# BlinkenPanel.net
KiCad netlist of a schematic drawn in EAGLE
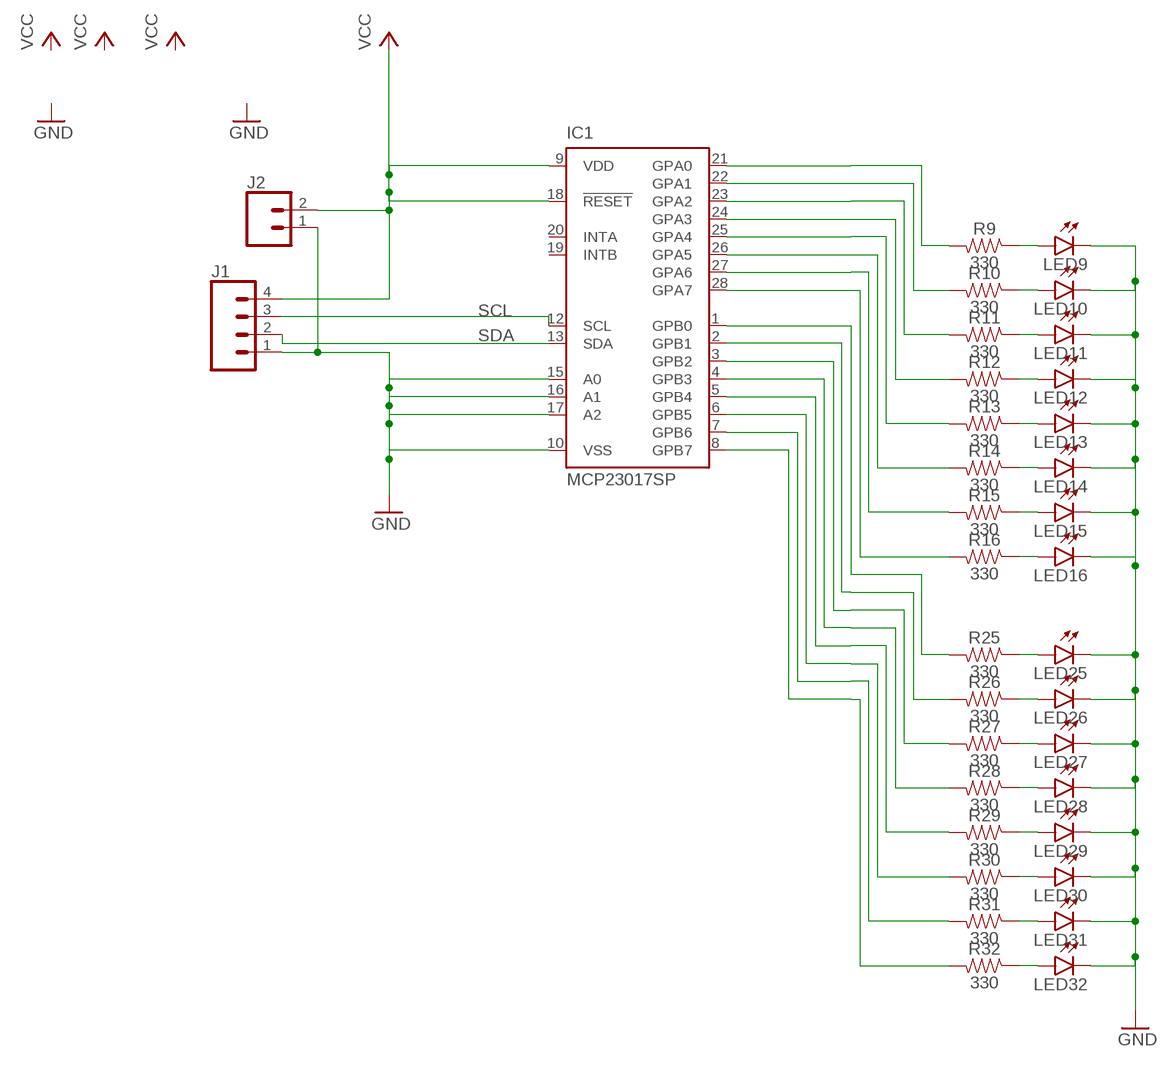
[diagram p0: schematic, sheet 1]

(export (version "E")
  (design (tool "Eeschema 10.0.6"))
  (components
    (comp (ref "IC1")
      (value "MCP23017SP")
      (footprint "eagle-import:DIL28-3")
      (fields (field (name "MF") "MICROCHIP") (field (name "MPN") "MCP23017-E/SP"))
      (libsource (lib "eagle-import") (part "MCP23017SP"))
    )
    (comp (ref "J1")
      (value "CONN_04LOCK")
      (footprint "eagle-import:1X04_LOCK")
      (libsource (lib "eagle-import") (part "CONN_04LOCK"))
    )
    (comp (ref "J2")
      (value "CONN_02")
      (footprint "eagle-import:1X02")
      (libsource (lib "eagle-import") (part "CONN_02"))
    )
    (comp (ref "LED9")
      (value "LED3MM")
      (footprint "eagle-import:LED3MM")
      (libsource (lib "eagle-import") (part "LED3MM"))
    )
    (comp (ref "LED10")
      (value "LED3MM")
      (footprint "eagle-import:LED3MM")
      (libsource (lib "eagle-import") (part "LED3MM"))
    )
    (comp (ref "LED11")
      (value "LED3MM")
      (footprint "eagle-import:LED3MM")
      (libsource (lib "eagle-import") (part "LED3MM"))
    )
    (comp (ref "LED12")
      (value "LED3MM")
      (footprint "eagle-import:LED3MM")
      (libsource (lib "eagle-import") (part "LED3MM"))
    )
    (comp (ref "LED13")
      (value "LED3MM")
      (footprint "eagle-import:LED3MM")
      (libsource (lib "eagle-import") (part "LED3MM"))
    )
    (comp (ref "LED14")
      (value "LED3MM")
      (footprint "eagle-import:LED3MM")
      (libsource (lib "eagle-import") (part "LED3MM"))
    )
    (comp (ref "LED15")
      (value "LED3MM")
      (footprint "eagle-import:LED3MM")
      (libsource (lib "eagle-import") (part "LED3MM"))
    )
    (comp (ref "LED16")
      (value "LED3MM")
      (footprint "eagle-import:LED3MM")
      (libsource (lib "eagle-import") (part "LED3MM"))
    )
    (comp (ref "LED25")
      (value "LED3MM")
      (footprint "eagle-import:LED3MM")
      (libsource (lib "eagle-import") (part "LED3MM"))
    )
    (comp (ref "LED26")
      (value "LED3MM")
      (footprint "eagle-import:LED3MM")
      (libsource (lib "eagle-import") (part "LED3MM"))
    )
    (comp (ref "LED27")
      (value "LED3MM")
      (footprint "eagle-import:LED3MM")
      (libsource (lib "eagle-import") (part "LED3MM"))
    )
    (comp (ref "LED28")
      (value "LED3MM")
      (footprint "eagle-import:LED3MM")
      (libsource (lib "eagle-import") (part "LED3MM"))
    )
    (comp (ref "LED29")
      (value "LED3MM")
      (footprint "eagle-import:LED3MM")
      (libsource (lib "eagle-import") (part "LED3MM"))
    )
    (comp (ref "LED30")
      (value "LED3MM")
      (footprint "eagle-import:LED3MM")
      (libsource (lib "eagle-import") (part "LED3MM"))
    )
    (comp (ref "LED31")
      (value "LED3MM")
      (footprint "eagle-import:LED3MM")
      (libsource (lib "eagle-import") (part "LED3MM"))
    )
    (comp (ref "LED32")
      (value "LED3MM")
      (footprint "eagle-import:LED3MM")
      (libsource (lib "eagle-import") (part "LED3MM"))
    )
    (comp (ref "R9")
      (value "330")
      (footprint "eagle-import:0603")
      (libsource (lib "eagle-import") (part "330OHM-0603-1/10W-1%"))
    )
    (comp (ref "R10")
      (value "330")
      (footprint "eagle-import:0603")
      (libsource (lib "eagle-import") (part "330OHM-0603-1/10W-1%"))
    )
    (comp (ref "R11")
      (value "330")
      (footprint "eagle-import:0603")
      (libsource (lib "eagle-import") (part "330OHM-0603-1/10W-1%"))
    )
    (comp (ref "R12")
      (value "330")
      (footprint "eagle-import:0603")
      (libsource (lib "eagle-import") (part "330OHM-0603-1/10W-1%"))
    )
    (comp (ref "R13")
      (value "330")
      (footprint "eagle-import:0603")
      (libsource (lib "eagle-import") (part "330OHM-0603-1/10W-1%"))
    )
    (comp (ref "R14")
      (value "330")
      (footprint "eagle-import:0603")
      (libsource (lib "eagle-import") (part "330OHM-0603-1/10W-1%"))
    )
    (comp (ref "R15")
      (value "330")
      (footprint "eagle-import:0603")
      (libsource (lib "eagle-import") (part "330OHM-0603-1/10W-1%"))
    )
    (comp (ref "R16")
      (value "330")
      (footprint "eagle-import:0603")
      (libsource (lib "eagle-import") (part "330OHM-0603-1/10W-1%"))
    )
    (comp (ref "R25")
      (value "330")
      (footprint "eagle-import:0603")
      (libsource (lib "eagle-import") (part "330OHM-0603-1/10W-1%"))
    )
    (comp (ref "R26")
      (value "330")
      (footprint "eagle-import:0603")
      (libsource (lib "eagle-import") (part "330OHM-0603-1/10W-1%"))
    )
    (comp (ref "R27")
      (value "330")
      (footprint "eagle-import:0603")
      (libsource (lib "eagle-import") (part "330OHM-0603-1/10W-1%"))
    )
    (comp (ref "R28")
      (value "330")
      (footprint "eagle-import:0603")
      (libsource (lib "eagle-import") (part "330OHM-0603-1/10W-1%"))
    )
    (comp (ref "R29")
      (value "330")
      (footprint "eagle-import:0603")
      (libsource (lib "eagle-import") (part "330OHM-0603-1/10W-1%"))
    )
    (comp (ref "R30")
      (value "330")
      (footprint "eagle-import:0603")
      (libsource (lib "eagle-import") (part "330OHM-0603-1/10W-1%"))
    )
    (comp (ref "R31")
      (value "330")
      (footprint "eagle-import:0603")
      (libsource (lib "eagle-import") (part "330OHM-0603-1/10W-1%"))
    )
    (comp (ref "R32")
      (value "330")
      (footprint "eagle-import:0603")
      (libsource (lib "eagle-import") (part "330OHM-0603-1/10W-1%"))
    )
  )
  (nets
    (net (code "1") (name "/SCL") (class "Default")
      (node (ref "IC1") (pin "12") (pinfunction "SCL_12") (pintype "input"))
      (node (ref "J1") (pin "3") (pinfunction "3_3") (pintype "passive"))
    )
    (net (code "2") (name "/SDA") (class "Default")
      (node (ref "IC1") (pin "13") (pinfunction "SDA_13") (pintype "bidirectional"))
      (node (ref "J1") (pin "2") (pinfunction "2_2") (pintype "passive"))
    )
    (net (code "3") (name "GND") (class "Default")
      (node (ref "IC1") (pin "10") (pinfunction "VSS_10") (pintype "power_in"))
      (node (ref "IC1") (pin "15") (pinfunction "A0_15") (pintype "input"))
      (node (ref "IC1") (pin "16") (pinfunction "A1_16") (pintype "input"))
      (node (ref "IC1") (pin "17") (pinfunction "A2_17") (pintype "input"))
      (node (ref "J1") (pin "1") (pinfunction "1_1") (pintype "passive"))
      (node (ref "J2") (pin "1") (pinfunction "1_1") (pintype "passive"))
      (node (ref "LED10") (pin "K") (pinfunction "C_K") (pintype "passive"))
      (node (ref "LED11") (pin "K") (pinfunction "C_K") (pintype "passive"))
      (node (ref "LED12") (pin "K") (pinfunction "C_K") (pintype "passive"))
      (node (ref "LED13") (pin "K") (pinfunction "C_K") (pintype "passive"))
      (node (ref "LED14") (pin "K") (pinfunction "C_K") (pintype "passive"))
      (node (ref "LED15") (pin "K") (pinfunction "C_K") (pintype "passive"))
      (node (ref "LED16") (pin "K") (pinfunction "C_K") (pintype "passive"))
      (node (ref "LED25") (pin "K") (pinfunction "C_K") (pintype "passive"))
      (node (ref "LED26") (pin "K") (pinfunction "C_K") (pintype "passive"))
      (node (ref "LED27") (pin "K") (pinfunction "C_K") (pintype "passive"))
      (node (ref "LED28") (pin "K") (pinfunction "C_K") (pintype "passive"))
      (node (ref "LED29") (pin "K") (pinfunction "C_K") (pintype "passive"))
      (node (ref "LED30") (pin "K") (pinfunction "C_K") (pintype "passive"))
      (node (ref "LED31") (pin "K") (pinfunction "C_K") (pintype "passive"))
      (node (ref "LED32") (pin "K") (pinfunction "C_K") (pintype "passive"))
      (node (ref "LED9") (pin "K") (pinfunction "C_K") (pintype "passive"))
    )
    (net (code "4") (name "Net-(IC1-GPA0)") (class "Default")
      (node (ref "IC1") (pin "21") (pinfunction "GPA0_21") (pintype "bidirectional"))
      (node (ref "R9") (pin "2") (pinfunction "2_2") (pintype "passive"))
    )
    (net (code "5") (name "Net-(IC1-GPA1)") (class "Default")
      (node (ref "IC1") (pin "22") (pinfunction "GPA1_22") (pintype "bidirectional"))
      (node (ref "R10") (pin "2") (pinfunction "2_2") (pintype "passive"))
    )
    (net (code "6") (name "Net-(IC1-GPA2)") (class "Default")
      (node (ref "IC1") (pin "23") (pinfunction "GPA2_23") (pintype "bidirectional"))
      (node (ref "R11") (pin "2") (pinfunction "2_2") (pintype "passive"))
    )
    (net (code "7") (name "Net-(IC1-GPA3)") (class "Default")
      (node (ref "IC1") (pin "24") (pinfunction "GPA3_24") (pintype "bidirectional"))
      (node (ref "R12") (pin "2") (pinfunction "2_2") (pintype "passive"))
    )
    (net (code "8") (name "Net-(IC1-GPA4)") (class "Default")
      (node (ref "IC1") (pin "25") (pinfunction "GPA4_25") (pintype "bidirectional"))
      (node (ref "R13") (pin "2") (pinfunction "2_2") (pintype "passive"))
    )
    (net (code "9") (name "Net-(IC1-GPA5)") (class "Default")
      (node (ref "IC1") (pin "26") (pinfunction "GPA5_26") (pintype "bidirectional"))
      (node (ref "R14") (pin "2") (pinfunction "2_2") (pintype "passive"))
    )
    (net (code "10") (name "Net-(IC1-GPA6)") (class "Default")
      (node (ref "IC1") (pin "27") (pinfunction "GPA6_27") (pintype "bidirectional"))
      (node (ref "R15") (pin "2") (pinfunction "2_2") (pintype "passive"))
    )
    (net (code "11") (name "Net-(IC1-GPA7)") (class "Default")
      (node (ref "IC1") (pin "28") (pinfunction "GPA7_28") (pintype "bidirectional"))
      (node (ref "R16") (pin "2") (pinfunction "2_2") (pintype "passive"))
    )
    (net (code "12") (name "Net-(IC1-GPB0)") (class "Default")
      (node (ref "IC1") (pin "1") (pinfunction "GPB0_1") (pintype "bidirectional"))
      (node (ref "R25") (pin "2") (pinfunction "2_2") (pintype "passive"))
    )
    (net (code "13") (name "Net-(IC1-GPB1)") (class "Default")
      (node (ref "IC1") (pin "2") (pinfunction "GPB1_2") (pintype "bidirectional"))
      (node (ref "R26") (pin "2") (pinfunction "2_2") (pintype "passive"))
    )
    (net (code "14") (name "Net-(IC1-GPB2)") (class "Default")
      (node (ref "IC1") (pin "3") (pinfunction "GPB2_3") (pintype "bidirectional"))
      (node (ref "R27") (pin "2") (pinfunction "2_2") (pintype "passive"))
    )
    (net (code "15") (name "Net-(IC1-GPB3)") (class "Default")
      (node (ref "IC1") (pin "4") (pinfunction "GPB3_4") (pintype "bidirectional"))
      (node (ref "R28") (pin "2") (pinfunction "2_2") (pintype "passive"))
    )
    (net (code "16") (name "Net-(IC1-GPB4)") (class "Default")
      (node (ref "IC1") (pin "5") (pinfunction "GPB4_5") (pintype "bidirectional"))
      (node (ref "R29") (pin "2") (pinfunction "2_2") (pintype "passive"))
    )
    (net (code "17") (name "Net-(IC1-GPB5)") (class "Default")
      (node (ref "IC1") (pin "6") (pinfunction "GPB5_6") (pintype "bidirectional"))
      (node (ref "R30") (pin "2") (pinfunction "2_2") (pintype "passive"))
    )
    (net (code "18") (name "Net-(IC1-GPB6)") (class "Default")
      (node (ref "IC1") (pin "7") (pinfunction "GPB6_7") (pintype "bidirectional"))
      (node (ref "R31") (pin "2") (pinfunction "2_2") (pintype "passive"))
    )
    (net (code "19") (name "Net-(IC1-GPB7)") (class "Default")
      (node (ref "IC1") (pin "8") (pinfunction "GPB7_8") (pintype "bidirectional"))
      (node (ref "R32") (pin "2") (pinfunction "2_2") (pintype "passive"))
    )
    (net (code "20") (name "Net-(LED9-PadA)") (class "Default")
      (node (ref "LED9") (pin "A") (pinfunction "A_A") (pintype "passive"))
      (node (ref "R9") (pin "1") (pinfunction "1_1") (pintype "passive"))
    )
    (net (code "21") (name "Net-(LED10-PadA)") (class "Default")
      (node (ref "LED10") (pin "A") (pinfunction "A_A") (pintype "passive"))
      (node (ref "R10") (pin "1") (pinfunction "1_1") (pintype "passive"))
    )
    (net (code "22") (name "Net-(LED11-PadA)") (class "Default")
      (node (ref "LED11") (pin "A") (pinfunction "A_A") (pintype "passive"))
      (node (ref "R11") (pin "1") (pinfunction "1_1") (pintype "passive"))
    )
    (net (code "23") (name "Net-(LED12-PadA)") (class "Default")
      (node (ref "LED12") (pin "A") (pinfunction "A_A") (pintype "passive"))
      (node (ref "R12") (pin "1") (pinfunction "1_1") (pintype "passive"))
    )
    (net (code "24") (name "Net-(LED13-PadA)") (class "Default")
      (node (ref "LED13") (pin "A") (pinfunction "A_A") (pintype "passive"))
      (node (ref "R13") (pin "1") (pinfunction "1_1") (pintype "passive"))
    )
    (net (code "25") (name "Net-(LED14-PadA)") (class "Default")
      (node (ref "LED14") (pin "A") (pinfunction "A_A") (pintype "passive"))
      (node (ref "R14") (pin "1") (pinfunction "1_1") (pintype "passive"))
    )
    (net (code "26") (name "Net-(LED15-PadA)") (class "Default")
      (node (ref "LED15") (pin "A") (pinfunction "A_A") (pintype "passive"))
      (node (ref "R15") (pin "1") (pinfunction "1_1") (pintype "passive"))
    )
    (net (code "27") (name "Net-(LED16-PadA)") (class "Default")
      (node (ref "LED16") (pin "A") (pinfunction "A_A") (pintype "passive"))
      (node (ref "R16") (pin "1") (pinfunction "1_1") (pintype "passive"))
    )
    (net (code "28") (name "Net-(LED25-PadA)") (class "Default")
      (node (ref "LED25") (pin "A") (pinfunction "A_A") (pintype "passive"))
      (node (ref "R25") (pin "1") (pinfunction "1_1") (pintype "passive"))
    )
    (net (code "29") (name "Net-(LED26-PadA)") (class "Default")
      (node (ref "LED26") (pin "A") (pinfunction "A_A") (pintype "passive"))
      (node (ref "R26") (pin "1") (pinfunction "1_1") (pintype "passive"))
    )
    (net (code "30") (name "Net-(LED27-PadA)") (class "Default")
      (node (ref "LED27") (pin "A") (pinfunction "A_A") (pintype "passive"))
      (node (ref "R27") (pin "1") (pinfunction "1_1") (pintype "passive"))
    )
    (net (code "31") (name "Net-(LED28-PadA)") (class "Default")
      (node (ref "LED28") (pin "A") (pinfunction "A_A") (pintype "passive"))
      (node (ref "R28") (pin "1") (pinfunction "1_1") (pintype "passive"))
    )
    (net (code "32") (name "Net-(LED29-PadA)") (class "Default")
      (node (ref "LED29") (pin "A") (pinfunction "A_A") (pintype "passive"))
      (node (ref "R29") (pin "1") (pinfunction "1_1") (pintype "passive"))
    )
    (net (code "33") (name "Net-(LED30-PadA)") (class "Default")
      (node (ref "LED30") (pin "A") (pinfunction "A_A") (pintype "passive"))
      (node (ref "R30") (pin "1") (pinfunction "1_1") (pintype "passive"))
    )
    (net (code "34") (name "Net-(LED31-PadA)") (class "Default")
      (node (ref "LED31") (pin "A") (pinfunction "A_A") (pintype "passive"))
      (node (ref "R31") (pin "1") (pinfunction "1_1") (pintype "passive"))
    )
    (net (code "35") (name "Net-(LED32-PadA)") (class "Default")
      (node (ref "LED32") (pin "A") (pinfunction "A_A") (pintype "passive"))
      (node (ref "R32") (pin "1") (pinfunction "1_1") (pintype "passive"))
    )
    (net (code "36") (name "VCC") (class "Default")
      (node (ref "IC1") (pin "18") (pinfunction "~{RESET}_18") (pintype "input"))
      (node (ref "IC1") (pin "9") (pinfunction "VDD_9") (pintype "power_in"))
      (node (ref "J1") (pin "4") (pinfunction "4_4") (pintype "passive"))
      (node (ref "J2") (pin "2") (pinfunction "2_2") (pintype "passive"))
    )
    (net (code "37") (name "unconnected-(IC1-INTA-Pad20)") (class "Default")
      (node (ref "IC1") (pin "20") (pinfunction "INTA_20") (pintype "output"))
    )
    (net (code "38") (name "unconnected-(IC1-INTB-Pad19)") (class "Default")
      (node (ref "IC1") (pin "19") (pinfunction "INTB_19") (pintype "output"))
    )
  )
)
